# Sensor_PCB_Electrochemical.net
KiCad netlist of a schematic drawn in EAGLE
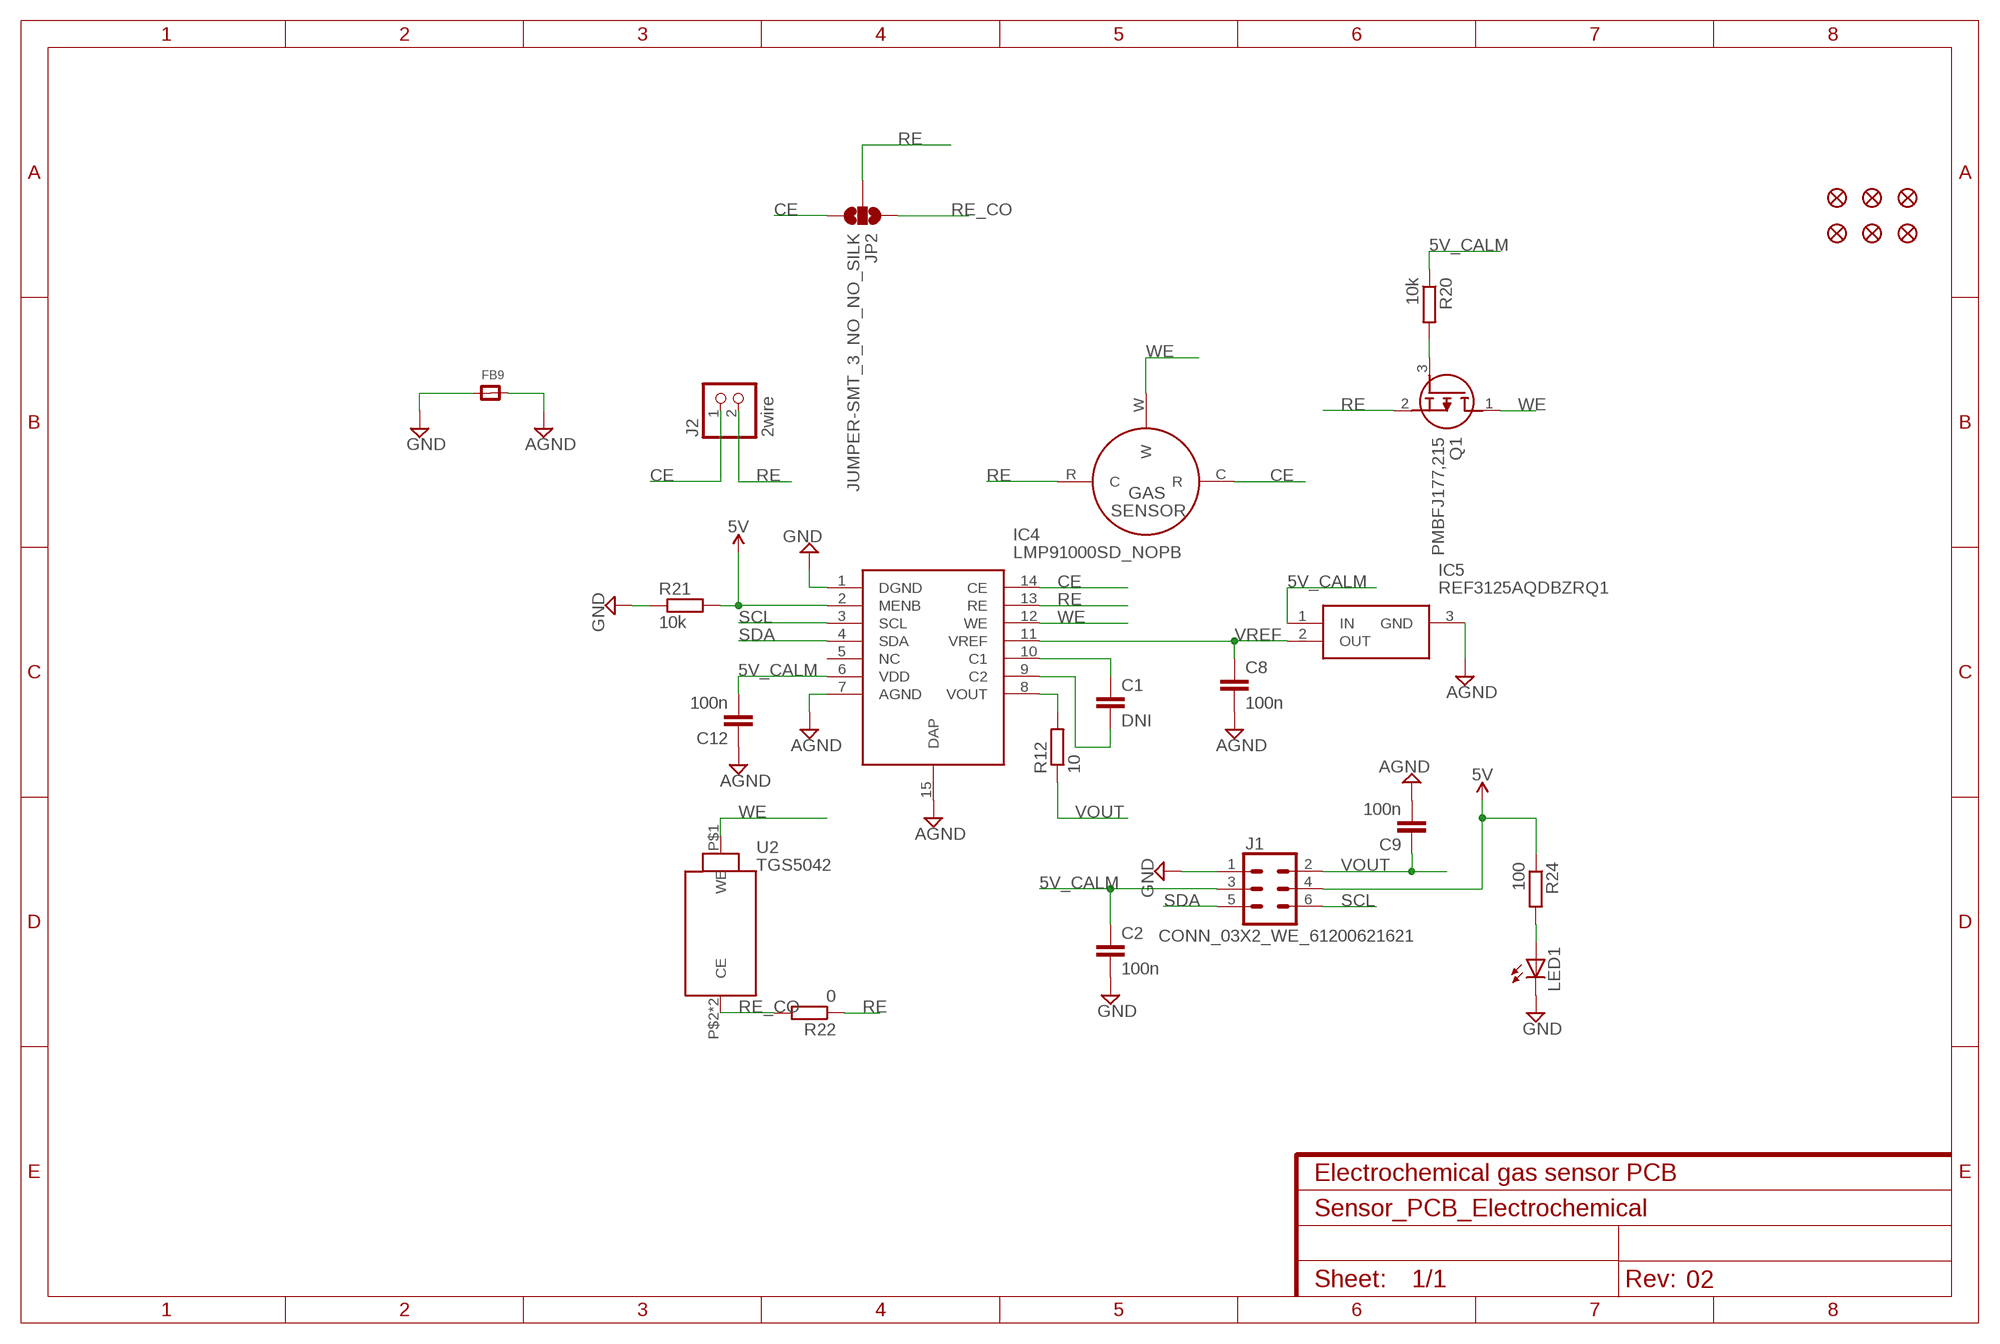
[diagram p0: schematic, sheet 1]

(export (version "E")
  (design (tool "Eeschema 10.0.6"))
  (components
    (comp (ref "C1")
      (value "DNI")
      (footprint "eagle-import:C0603K")
      (libsource (lib "eagle-import") (part "C-EUC0603K"))
    )
    (comp (ref "C2")
      (value "100n")
      (footprint "eagle-import:C0603K")
      (fields (field (name "PARTNO") "GRM188R71C104KA01D"))
      (libsource (lib "eagle-import") (part "C-EUC0603K"))
    )
    (comp (ref "C8")
      (value "100n")
      (footprint "eagle-import:C0603K")
      (fields (field (name "PARTNO") "GRM188R71C104KA01D"))
      (libsource (lib "eagle-import") (part "C-EUC0603K"))
    )
    (comp (ref "C9")
      (value "100n")
      (footprint "eagle-import:C0603K")
      (fields (field (name "PARTNO") "GRM188R71C104KA01D"))
      (libsource (lib "eagle-import") (part "C-EUC0603K"))
    )
    (comp (ref "C12")
      (value "100n")
      (footprint "eagle-import:C0603K")
      (fields (field (name "PARTNO") "GRM188R71C104KA01D"))
      (libsource (lib "eagle-import") (part "C-EUC0603K"))
    )
    (comp (ref "FB9")
      (value "FERRITE")
      (footprint "eagle-import:0603")
      (fields (field (name "PARTNO") "BLM18PG121SN1D"))
      (libsource (lib "eagle-import") (part "FERRITE"))
    )
    (comp (ref "FID3")
      (value "FIDUCIAL1X1UNMASKED")
      (footprint "eagle-import:FIDUCIAL_1MM_UNMASKED")
      (libsource (lib "eagle-import") (part "FIDUCIAL1X1UNMASKED"))
    )
    (comp (ref "FID5")
      (value "FIDUCIAL1X1UNMASKED")
      (footprint "eagle-import:FIDUCIAL_1MM_UNMASKED")
      (libsource (lib "eagle-import") (part "FIDUCIAL1X1UNMASKED"))
    )
    (comp (ref "FID6")
      (value "FIDUCIAL1X1UNMASKED")
      (footprint "eagle-import:FIDUCIAL_1MM_UNMASKED")
      (libsource (lib "eagle-import") (part "FIDUCIAL1X1UNMASKED"))
    )
    (comp (ref "FID7")
      (value "FIDUCIAL1X1UNMASKED")
      (footprint "eagle-import:FIDUCIAL_1MM_UNMASKED")
      (libsource (lib "eagle-import") (part "FIDUCIAL1X1UNMASKED"))
    )
    (comp (ref "FID8")
      (value "FIDUCIAL1X1UNMASKED")
      (footprint "eagle-import:FIDUCIAL_1MM_UNMASKED")
      (libsource (lib "eagle-import") (part "FIDUCIAL1X1UNMASKED"))
    )
    (comp (ref "FID9")
      (value "FIDUCIAL1X1UNMASKED")
      (footprint "eagle-import:FIDUCIAL_1MM_UNMASKED")
      (libsource (lib "eagle-import") (part "FIDUCIAL1X1UNMASKED"))
    )
    (comp (ref "IC4")
      (value "LMP91000SD_NOPB")
      (footprint "eagle-import:SON50P400X400X80-15N")
      (fields
        (field (name "MANUFACTURER_PART_NUMBER") "LMP91000SD/NOPB")
        (field (name "MOUSER_PART_NUMBER") "926-LMP91000SD/NOPB")
        (field (name "PARTNO") "LMP91000")
      )
      (libsource (lib "eagle-import") (part "LMP91000SD_NOPB"))
    )
    (comp (ref "IC5")
      (value "REF3125AQDBZRQ1")
      (footprint "eagle-import:SOT95P237X112-3N")
      (fields (field (name "MOUSER_PART_NUMBER") "595-REF3125AQDBZRQ1"))
      (libsource (lib "eagle-import") (part "REF3125AQDBZRQ1"))
    )
    (comp (ref "J1")
      (value "CONN_03X2_WE_61200621621")
      (footprint "eagle-import:WE_61200621621")
      (fields (field (name "PARTNO") "30306-6002HB"))
      (libsource (lib "eagle-import") (part "CONN_03X2_WE_61200621621"))
    )
    (comp (ref "J2")
      (value "2wire")
      (footprint "eagle-import:1X02")
      (fields (field (name "PARTNO") "TSW-102-07-G-S"))
      (libsource (lib "eagle-import") (part "PINHD-1X2"))
    )
    (comp (ref "JP2")
      (value "JUMPER-SMT_3_NO_NO_SILK")
      (footprint "eagle-import:SMT-JUMPER_3_0-NO_TRACE_NO-SILK")
      (libsource (lib "eagle-import") (part "JUMPER-SMT_3_NO_NO_SILK"))
    )
    (comp (ref "LED1")
      (value "LEDCHIP-LED0603")
      (footprint "eagle-import:CHIP-LED0603")
      (fields (field (name "PARTNO") "IN-S63AT5G"))
      (libsource (lib "eagle-import") (part "LEDCHIP-LED0603"))
    )
    (comp (ref "Q1")
      (value "PMBFJ177,215")
      (footprint "eagle-import:SOT95P230X110-3N")
      (fields (field (name "MOUSER_PART_NUMBER") "771-PMBFJ177-T/R"))
      (libsource (lib "eagle-import") (part "PMBFJ177,215"))
    )
    (comp (ref "R12")
      (value "10")
      (footprint "eagle-import:R0603")
      (fields (field (name "PARTNO") "CRCW060310R0FKEA"))
      (libsource (lib "eagle-import") (part "R-EU_R0603"))
    )
    (comp (ref "R20")
      (value "10k")
      (footprint "eagle-import:R0603")
      (fields (field (name "PARTNO") "CRCW060310K0FKEA"))
      (libsource (lib "eagle-import") (part "R-EU_R0603"))
    )
    (comp (ref "R21")
      (value "10k")
      (footprint "eagle-import:R0603")
      (fields (field (name "PARTNO") "CRCW060310K0FKEA"))
      (libsource (lib "eagle-import") (part "R-EU_R0603"))
    )
    (comp (ref "R22")
      (value "0")
      (footprint "eagle-import:R0603")
      (fields (field (name "PARTNO") "CRCW06030000Z0EA"))
      (libsource (lib "eagle-import") (part "R-EU_R0603"))
    )
    (comp (ref "R24")
      (value "100")
      (footprint "eagle-import:R0603")
      (fields (field (name "PARTNO") "CRCW0603100RFKEA"))
      (libsource (lib "eagle-import") (part "R-EU_R0603"))
    )
    (comp (ref "U2")
      (value "TGS5042")
      (footprint "eagle-import:TGS5042")
      (fields (field (name "PARTNO") "INSTALLED_BY_CUSTOMER"))
      (libsource (lib "eagle-import") (part "TGS5042"))
    )
    (comp (ref "X1")
      (value "3-ELECTRODE-GAS-SENSOR_SOCKET")
      (footprint "eagle-import:3-ELE_SOCKET_ANDON")
      (fields (field (name "PARTNO") "INSTALLED_BY_CUSTOMER"))
      (libsource (lib "eagle-import") (part "3-ELECTRODE-GAS-SENSOR_SOCKET"))
    )
  )
  (nets
    (net (code "1") (name "/5V_CALM") (class "Default")
      (node (ref "C12") (pin "2") (pinfunction "2_2") (pintype "passive"))
      (node (ref "C2") (pin "1") (pinfunction "1_1") (pintype "passive"))
      (node (ref "IC4") (pin "6") (pinfunction "VDD_6") (pintype "power_in"))
      (node (ref "IC5") (pin "1") (pinfunction "IN_1") (pintype "bidirectional"))
      (node (ref "J1") (pin "3") (pinfunction "3_3") (pintype "bidirectional"))
      (node (ref "R20") (pin "1") (pinfunction "1_1") (pintype "passive"))
    )
    (net (code "2") (name "/CE") (class "Default")
      (node (ref "IC4") (pin "14") (pinfunction "CE_14") (pintype "input"))
      (node (ref "J2") (pin "1") (pinfunction "1_1") (pintype "passive"))
      (node (ref "JP2") (pin "3") (pinfunction "3_3") (pintype "passive"))
      (node (ref "X1") (pin "C") (pinfunction "R_C") (pintype "bidirectional"))
    )
    (net (code "3") (name "/RE") (class "Default")
      (node (ref "IC4") (pin "13") (pinfunction "RE_13") (pintype "input"))
      (node (ref "J2") (pin "2") (pinfunction "2_2") (pintype "passive"))
      (node (ref "JP2") (pin "2") (pinfunction "2_2") (pintype "passive"))
      (node (ref "Q1") (pin "2") (pinfunction "S_2") (pintype "bidirectional"))
      (node (ref "R22") (pin "1") (pinfunction "1_1") (pintype "passive"))
      (node (ref "X1") (pin "R") (pinfunction "C_R") (pintype "bidirectional"))
    )
    (net (code "4") (name "/RE_CO") (class "Default")
      (node (ref "JP2") (pin "1") (pinfunction "1_1") (pintype "passive"))
      (node (ref "R22") (pin "2") (pinfunction "2_2") (pintype "passive"))
      (node (ref "U2") (pin "P$2") (pinfunction "CE_P$2") (pintype "bidirectional"))
      (node (ref "U2") (pin "P$3") (pinfunction "CE_P$3") (pintype "bidirectional"))
    )
    (net (code "5") (name "/SCL") (class "Default")
      (node (ref "IC4") (pin "3") (pinfunction "SCL_3") (pintype "input"))
      (node (ref "J1") (pin "6") (pinfunction "6_6") (pintype "bidirectional"))
    )
    (net (code "6") (name "/SDA") (class "Default")
      (node (ref "IC4") (pin "4") (pinfunction "SDA_4") (pintype "bidirectional"))
      (node (ref "J1") (pin "5") (pinfunction "5_5") (pintype "bidirectional"))
    )
    (net (code "7") (name "/VOUT") (class "Default")
      (node (ref "C9") (pin "1") (pinfunction "1_1") (pintype "passive"))
      (node (ref "J1") (pin "2") (pinfunction "2_2") (pintype "bidirectional"))
      (node (ref "R12") (pin "1") (pinfunction "1_1") (pintype "passive"))
    )
    (net (code "8") (name "/VREF") (class "Default")
      (node (ref "C8") (pin "1") (pinfunction "1_1") (pintype "passive"))
      (node (ref "IC4") (pin "11") (pinfunction "VREF_11") (pintype "input"))
      (node (ref "IC5") (pin "2") (pinfunction "OUT_2") (pintype "bidirectional"))
    )
    (net (code "9") (name "/WE") (class "Default")
      (node (ref "IC4") (pin "12") (pinfunction "WE_12") (pintype "input"))
      (node (ref "Q1") (pin "1") (pinfunction "D_1") (pintype "bidirectional"))
      (node (ref "U2") (pin "P$1") (pinfunction "WE_P$1") (pintype "bidirectional"))
      (node (ref "X1") (pin "W") (pinfunction "W_W") (pintype "bidirectional"))
    )
    (net (code "10") (name "5V") (class "Default")
      (node (ref "IC4") (pin "2") (pinfunction "MENB_2") (pintype "input"))
      (node (ref "J1") (pin "4") (pinfunction "4_4") (pintype "bidirectional"))
      (node (ref "R21") (pin "2") (pinfunction "2_2") (pintype "passive"))
      (node (ref "R24") (pin "1") (pinfunction "1_1") (pintype "passive"))
    )
    (net (code "11") (name "AGND") (class "Default")
      (node (ref "C12") (pin "1") (pinfunction "1_1") (pintype "passive"))
      (node (ref "C8") (pin "2") (pinfunction "2_2") (pintype "passive"))
      (node (ref "C9") (pin "2") (pinfunction "2_2") (pintype "passive"))
      (node (ref "FB9") (pin "2") (pinfunction "P$2_2") (pintype "passive"))
      (node (ref "IC4") (pin "15") (pinfunction "DAP_15") (pintype "power_in"))
      (node (ref "IC4") (pin "7") (pinfunction "AGND_7") (pintype "power_in"))
      (node (ref "IC5") (pin "3") (pinfunction "GND_3") (pintype "bidirectional"))
    )
    (net (code "12") (name "GND") (class "Default")
      (node (ref "C2") (pin "2") (pinfunction "2_2") (pintype "passive"))
      (node (ref "FB9") (pin "1") (pinfunction "P$1_1") (pintype "passive"))
      (node (ref "IC4") (pin "1") (pinfunction "DGND_1") (pintype "power_in"))
      (node (ref "J1") (pin "1") (pinfunction "1_1") (pintype "bidirectional"))
      (node (ref "LED1") (pin "C") (pinfunction "C_C") (pintype "passive"))
      (node (ref "R21") (pin "1") (pinfunction "1_1") (pintype "passive"))
    )
    (net (code "13") (name "Net-(IC4-C1)") (class "Default")
      (node (ref "C1") (pin "1") (pinfunction "1_1") (pintype "passive"))
      (node (ref "IC4") (pin "10") (pinfunction "C1_10") (pintype "bidirectional"))
    )
    (net (code "14") (name "Net-(IC4-C2)") (class "Default")
      (node (ref "C1") (pin "2") (pinfunction "2_2") (pintype "passive"))
      (node (ref "IC4") (pin "9") (pinfunction "C2_9") (pintype "bidirectional"))
    )
    (net (code "15") (name "Net-(IC4-VOUT)") (class "Default")
      (node (ref "IC4") (pin "8") (pinfunction "VOUT_8") (pintype "output"))
      (node (ref "R12") (pin "2") (pinfunction "2_2") (pintype "passive"))
    )
    (net (code "16") (name "Net-(LED1-PadA)") (class "Default")
      (node (ref "LED1") (pin "A") (pinfunction "A_A") (pintype "passive"))
      (node (ref "R24") (pin "2") (pinfunction "2_2") (pintype "passive"))
    )
    (net (code "17") (name "Net-(Q1-G)") (class "Default")
      (node (ref "Q1") (pin "3") (pinfunction "G_3") (pintype "bidirectional"))
      (node (ref "R20") (pin "2") (pinfunction "2_2") (pintype "passive"))
    )
    (net (code "18") (name "unconnected-(IC4-NC-Pad5)") (class "Default")
      (node (ref "IC4") (pin "5") (pinfunction "NC_5") (pintype "no_connect"))
    )
  )
)
